# Motors.net
KiCad netlist of a schematic drawn in Altium Designer
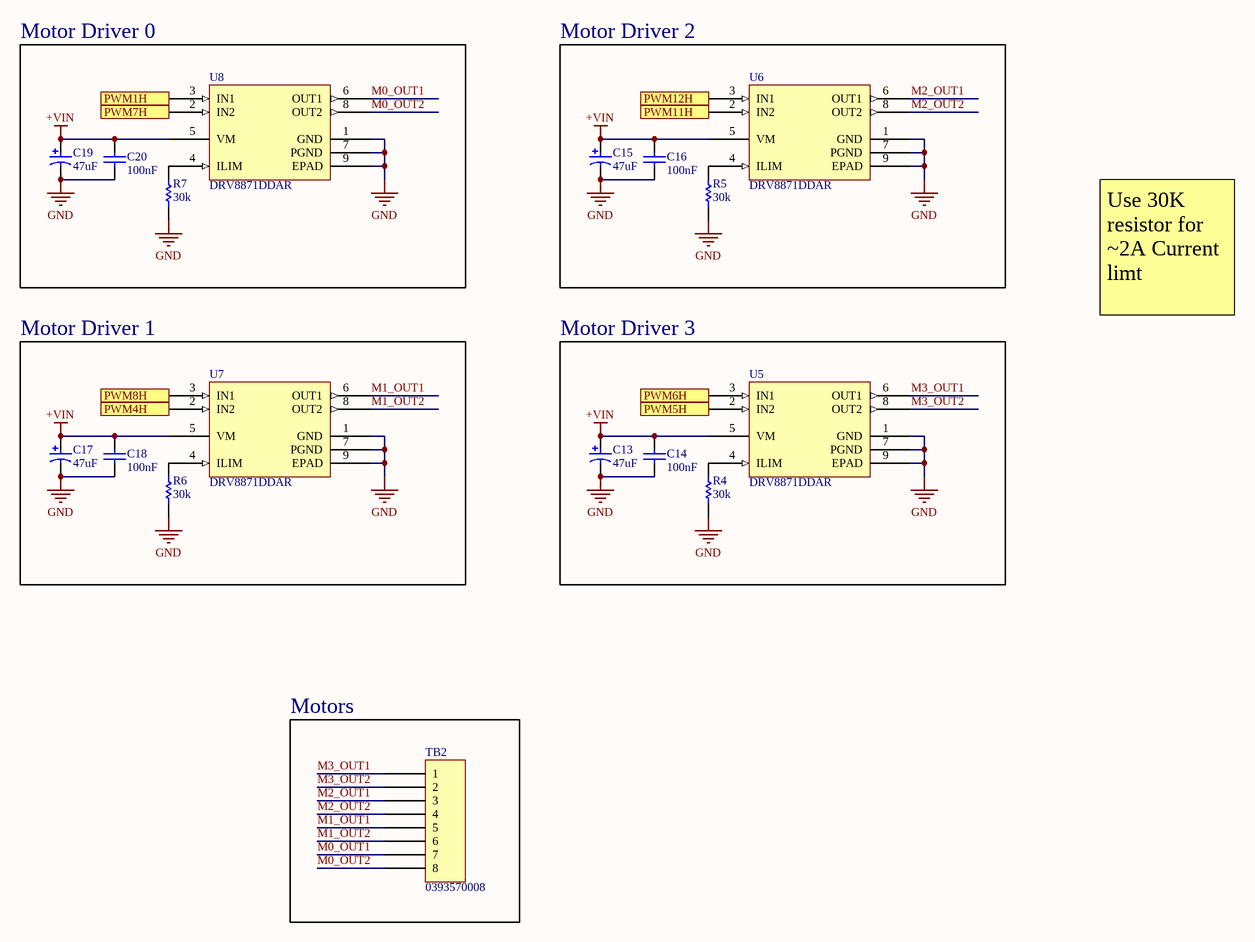
[diagram p0: Motors.SchDoc]

(export (version "E")
  (design (tool "Eeschema 10.0.6"))
  (components
    (comp (ref "C13")
      (value "47uF")
      (footprint "EEE-FT1C470AR")
      (fields
        (field (name "MANUFACTURER") "Panasonic")
        (field (name "MANUFACTURER PART NUMBER") "EEEFT1C470AR")
        (field (name "VOLTAGE") "16V")
      )
      (libsource (lib "altium-library") (part "EEE-FT1C470AR"))
    )
    (comp (ref "C14")
      (value "100nF")
      (footprint "0402")
      (description "TDK - C1005X7R1C104K050BC. - CERAMIC CAPACITOR, 0.1UF, 16V, X7R, 10%, 0402, FULL REEL")
      (fields
        (field (name "MANUFACTURER") "TDK")
        (field (name "MANUFACTURER PART NUMBER") "C1005X7R1C104K050BC")
      )
      (libsource (lib "altium-library") (part "Capacitor"))
    )
    (comp (ref "C15")
      (value "47uF")
      (footprint "EEE-FT1C470AR")
      (fields
        (field (name "MANUFACTURER") "Panasonic")
        (field (name "MANUFACTURER PART NUMBER") "EEEFT1C470AR")
        (field (name "VOLTAGE") "16V")
      )
      (libsource (lib "altium-library") (part "EEE-FT1C470AR"))
    )
    (comp (ref "C16")
      (value "100nF")
      (footprint "0402")
      (description "TDK - C1005X7R1C104K050BC. - CERAMIC CAPACITOR, 0.1UF, 16V, X7R, 10%, 0402, FULL REEL")
      (fields
        (field (name "MANUFACTURER") "TDK")
        (field (name "MANUFACTURER PART NUMBER") "C1005X7R1C104K050BC")
      )
      (libsource (lib "altium-library") (part "Capacitor"))
    )
    (comp (ref "C17")
      (value "47uF")
      (footprint "EEE-FT1C470AR")
      (fields
        (field (name "MANUFACTURER") "Panasonic")
        (field (name "MANUFACTURER PART NUMBER") "EEEFT1C470AR")
        (field (name "VOLTAGE") "16V")
      )
      (libsource (lib "altium-library") (part "EEE-FT1C470AR"))
    )
    (comp (ref "C18")
      (value "100nF")
      (footprint "0402")
      (description "TDK - C1005X7R1C104K050BC. - CERAMIC CAPACITOR, 0.1UF, 16V, X7R, 10%, 0402, FULL REEL")
      (fields
        (field (name "MANUFACTURER") "TDK")
        (field (name "MANUFACTURER PART NUMBER") "C1005X7R1C104K050BC")
      )
      (libsource (lib "altium-library") (part "Capacitor"))
    )
    (comp (ref "C19")
      (value "47uF")
      (footprint "EEE-FT1C470AR")
      (fields
        (field (name "MANUFACTURER") "Panasonic")
        (field (name "MANUFACTURER PART NUMBER") "EEEFT1C470AR")
        (field (name "VOLTAGE") "16V")
      )
      (libsource (lib "altium-library") (part "EEE-FT1C470AR"))
    )
    (comp (ref "C20")
      (value "100nF")
      (footprint "0402")
      (description "TDK - C1005X7R1C104K050BC. - CERAMIC CAPACITOR, 0.1UF, 16V, X7R, 10%, 0402, FULL REEL")
      (fields
        (field (name "MANUFACTURER") "TDK")
        (field (name "MANUFACTURER PART NUMBER") "C1005X7R1C104K050BC")
      )
      (libsource (lib "altium-library") (part "Capacitor"))
    )
    (comp (ref "R4")
      (value "30k")
      (footprint "0402")
      (description "Res Thick Film 0402 30K Ohm 1% 0.063W(1/16W) ±100ppm/C Molded SMD Automotive Paper T/R")
      (fields
        (field (name "MANUFACTURER") "Vishay")
        (field (name "MANUFACTURER PART NUMBER") "CRCW040230K0FKED")
      )
      (libsource (lib "altium-library") (part "Resistor"))
    )
    (comp (ref "R5")
      (value "30k")
      (footprint "0402")
      (description "Res Thick Film 0402 30K Ohm 1% 0.063W(1/16W) ±100ppm/C Molded SMD Automotive Paper T/R")
      (fields
        (field (name "MANUFACTURER") "Vishay")
        (field (name "MANUFACTURER PART NUMBER") "CRCW040230K0FKED")
      )
      (libsource (lib "altium-library") (part "Resistor"))
    )
    (comp (ref "R6")
      (value "30k")
      (footprint "0402")
      (description "Res Thick Film 0402 30K Ohm 1% 0.063W(1/16W) ±100ppm/C Molded SMD Automotive Paper T/R")
      (fields
        (field (name "MANUFACTURER") "Vishay")
        (field (name "MANUFACTURER PART NUMBER") "CRCW040230K0FKED")
      )
      (libsource (lib "altium-library") (part "Resistor"))
    )
    (comp (ref "R7")
      (value "30k")
      (footprint "0402")
      (description "Res Thick Film 0402 30K Ohm 1% 0.063W(1/16W) ±100ppm/C Molded SMD Automotive Paper T/R")
      (fields
        (field (name "MANUFACTURER") "Vishay")
        (field (name "MANUFACTURER PART NUMBER") "CRCW040230K0FKED")
      )
      (libsource (lib "altium-library") (part "Resistor"))
    )
    (comp (ref "TB2")
      (value "0393570008")
      (footprint "0393570008")
      (description "Conn Eurostyle Block 8 POS 3.5mm Solder ST Thru-Hole 17.5A/Contact")
      (fields (field (name "MANUFACTURER") "Molex") (field (name "VOLTAGE") "300V"))
      (libsource (lib "altium-library") (part "0393570008"))
    )
    (comp (ref "U5")
      (value "DRV8871DDAR")
      (footprint "8-HSOP")
      (description "IC BRUSHED DC MOTOR 8SOIC")
      (fields (field (name "MANUFACTURER") "Texas Instruments"))
      (libsource (lib "altium-library") (part "DRV8871DDAR"))
    )
    (comp (ref "U6")
      (value "DRV8871DDAR")
      (footprint "8-HSOP")
      (description "IC BRUSHED DC MOTOR 8SOIC")
      (fields (field (name "MANUFACTURER") "Texas Instruments"))
      (libsource (lib "altium-library") (part "DRV8871DDAR"))
    )
    (comp (ref "U7")
      (value "DRV8871DDAR")
      (footprint "8-HSOP")
      (description "IC BRUSHED DC MOTOR 8SOIC")
      (fields (field (name "MANUFACTURER") "Texas Instruments"))
      (libsource (lib "altium-library") (part "DRV8871DDAR"))
    )
    (comp (ref "U8")
      (value "DRV8871DDAR")
      (footprint "8-HSOP")
      (description "IC BRUSHED DC MOTOR 8SOIC")
      (fields (field (name "MANUFACTURER") "Texas Instruments"))
      (libsource (lib "altium-library") (part "DRV8871DDAR"))
    )
  )
  (nets
    (net (code "1") (name "+VIN") (class "Default")
      (node (ref "C13") (pin "1") (pinfunction "1_1") (pintype "passive"))
      (node (ref "C14") (pin "2") (pinfunction "2_2") (pintype "passive"))
      (node (ref "C15") (pin "1") (pinfunction "1_1") (pintype "passive"))
      (node (ref "C16") (pin "2") (pinfunction "2_2") (pintype "passive"))
      (node (ref "C17") (pin "1") (pinfunction "1_1") (pintype "passive"))
      (node (ref "C18") (pin "2") (pinfunction "2_2") (pintype "passive"))
      (node (ref "C19") (pin "1") (pinfunction "1_1") (pintype "passive"))
      (node (ref "C20") (pin "2") (pinfunction "2_2") (pintype "passive"))
      (node (ref "U5") (pin "5") (pinfunction "VM_5") (pintype "power_in"))
      (node (ref "U6") (pin "5") (pinfunction "VM_5") (pintype "power_in"))
      (node (ref "U7") (pin "5") (pinfunction "VM_5") (pintype "power_in"))
      (node (ref "U8") (pin "5") (pinfunction "VM_5") (pintype "power_in"))
    )
    (net (code "2") (name "/M0_OUT1") (class "Default")
      (node (ref "TB2") (pin "7") (pinfunction "7_7") (pintype "passive"))
      (node (ref "U8") (pin "6") (pinfunction "OUT1_6") (pintype "output"))
    )
    (net (code "3") (name "/M0_OUT2") (class "Default")
      (node (ref "TB2") (pin "8") (pinfunction "8_8") (pintype "passive"))
      (node (ref "U8") (pin "8") (pinfunction "OUT2_8") (pintype "output"))
    )
    (net (code "4") (name "/M1_OUT1") (class "Default")
      (node (ref "TB2") (pin "5") (pinfunction "5_5") (pintype "passive"))
      (node (ref "U7") (pin "6") (pinfunction "OUT1_6") (pintype "output"))
    )
    (net (code "5") (name "/M1_OUT2") (class "Default")
      (node (ref "TB2") (pin "6") (pinfunction "6_6") (pintype "passive"))
      (node (ref "U7") (pin "8") (pinfunction "OUT2_8") (pintype "output"))
    )
    (net (code "6") (name "/M2_OUT1") (class "Default")
      (node (ref "TB2") (pin "3") (pinfunction "3_3") (pintype "passive"))
      (node (ref "U6") (pin "6") (pinfunction "OUT1_6") (pintype "output"))
    )
    (net (code "7") (name "/M2_OUT2") (class "Default")
      (node (ref "TB2") (pin "4") (pinfunction "4_4") (pintype "passive"))
      (node (ref "U6") (pin "8") (pinfunction "OUT2_8") (pintype "output"))
    )
    (net (code "8") (name "/M3_OUT1") (class "Default")
      (node (ref "TB2") (pin "1") (pinfunction "1_1") (pintype "passive"))
      (node (ref "U5") (pin "6") (pinfunction "OUT1_6") (pintype "output"))
    )
    (net (code "9") (name "/M3_OUT2") (class "Default")
      (node (ref "TB2") (pin "2") (pinfunction "2_2") (pintype "passive"))
      (node (ref "U5") (pin "8") (pinfunction "OUT2_8") (pintype "output"))
    )
    (net (code "10") (name "/PWM1H") (class "Default")
      (node (ref "U8") (pin "3") (pinfunction "IN1_3") (pintype "input"))
    )
    (net (code "11") (name "/PWM4H") (class "Default")
      (node (ref "U7") (pin "2") (pinfunction "IN2_2") (pintype "input"))
    )
    (net (code "12") (name "/PWM5H") (class "Default")
      (node (ref "U5") (pin "2") (pinfunction "IN2_2") (pintype "input"))
    )
    (net (code "13") (name "/PWM6H") (class "Default")
      (node (ref "U5") (pin "3") (pinfunction "IN1_3") (pintype "input"))
    )
    (net (code "14") (name "/PWM7H") (class "Default")
      (node (ref "U8") (pin "2") (pinfunction "IN2_2") (pintype "input"))
    )
    (net (code "15") (name "/PWM8H") (class "Default")
      (node (ref "U7") (pin "3") (pinfunction "IN1_3") (pintype "input"))
    )
    (net (code "16") (name "/PWM11H") (class "Default")
      (node (ref "U6") (pin "2") (pinfunction "IN2_2") (pintype "input"))
    )
    (net (code "17") (name "/PWM12H") (class "Default")
      (node (ref "U6") (pin "3") (pinfunction "IN1_3") (pintype "input"))
    )
    (net (code "18") (name "GND") (class "Default")
      (node (ref "C13") (pin "2") (pinfunction "2_2") (pintype "passive"))
      (node (ref "C14") (pin "1") (pinfunction "1_1") (pintype "passive"))
      (node (ref "C15") (pin "2") (pinfunction "2_2") (pintype "passive"))
      (node (ref "C16") (pin "1") (pinfunction "1_1") (pintype "passive"))
      (node (ref "C17") (pin "2") (pinfunction "2_2") (pintype "passive"))
      (node (ref "C18") (pin "1") (pinfunction "1_1") (pintype "passive"))
      (node (ref "C19") (pin "2") (pinfunction "2_2") (pintype "passive"))
      (node (ref "C20") (pin "1") (pinfunction "1_1") (pintype "passive"))
      (node (ref "R4") (pin "1") (pinfunction "1_1") (pintype "passive"))
      (node (ref "R5") (pin "1") (pinfunction "1_1") (pintype "passive"))
      (node (ref "R6") (pin "1") (pinfunction "1_1") (pintype "passive"))
      (node (ref "R7") (pin "1") (pinfunction "1_1") (pintype "passive"))
      (node (ref "U5") (pin "1") (pinfunction "GND_1") (pintype "power_in"))
      (node (ref "U5") (pin "7") (pinfunction "PGND_7") (pintype "power_in"))
      (node (ref "U5") (pin "9") (pinfunction "EPAD_9") (pintype "power_in"))
      (node (ref "U6") (pin "1") (pinfunction "GND_1") (pintype "power_in"))
      (node (ref "U6") (pin "7") (pinfunction "PGND_7") (pintype "power_in"))
      (node (ref "U6") (pin "9") (pinfunction "EPAD_9") (pintype "power_in"))
      (node (ref "U7") (pin "1") (pinfunction "GND_1") (pintype "power_in"))
      (node (ref "U7") (pin "7") (pinfunction "PGND_7") (pintype "power_in"))
      (node (ref "U7") (pin "9") (pinfunction "EPAD_9") (pintype "power_in"))
      (node (ref "U8") (pin "1") (pinfunction "GND_1") (pintype "power_in"))
      (node (ref "U8") (pin "7") (pinfunction "PGND_7") (pintype "power_in"))
      (node (ref "U8") (pin "9") (pinfunction "EPAD_9") (pintype "power_in"))
    )
    (net (code "19") (name "Net-(U5-ILIM)") (class "Default")
      (node (ref "R4") (pin "2") (pinfunction "2_2") (pintype "passive"))
      (node (ref "U5") (pin "4") (pinfunction "ILIM_4") (pintype "input"))
    )
    (net (code "20") (name "Net-(U6-ILIM)") (class "Default")
      (node (ref "R5") (pin "2") (pinfunction "2_2") (pintype "passive"))
      (node (ref "U6") (pin "4") (pinfunction "ILIM_4") (pintype "input"))
    )
    (net (code "21") (name "Net-(U7-ILIM)") (class "Default")
      (node (ref "R6") (pin "2") (pinfunction "2_2") (pintype "passive"))
      (node (ref "U7") (pin "4") (pinfunction "ILIM_4") (pintype "input"))
    )
    (net (code "22") (name "Net-(U8-ILIM)") (class "Default")
      (node (ref "R7") (pin "2") (pinfunction "2_2") (pintype "passive"))
      (node (ref "U8") (pin "4") (pinfunction "ILIM_4") (pintype "input"))
    )
  )
)
